# LEO_COTS_amps_rev1.net
KiCad netlist of a schematic drawn in Altium Designer
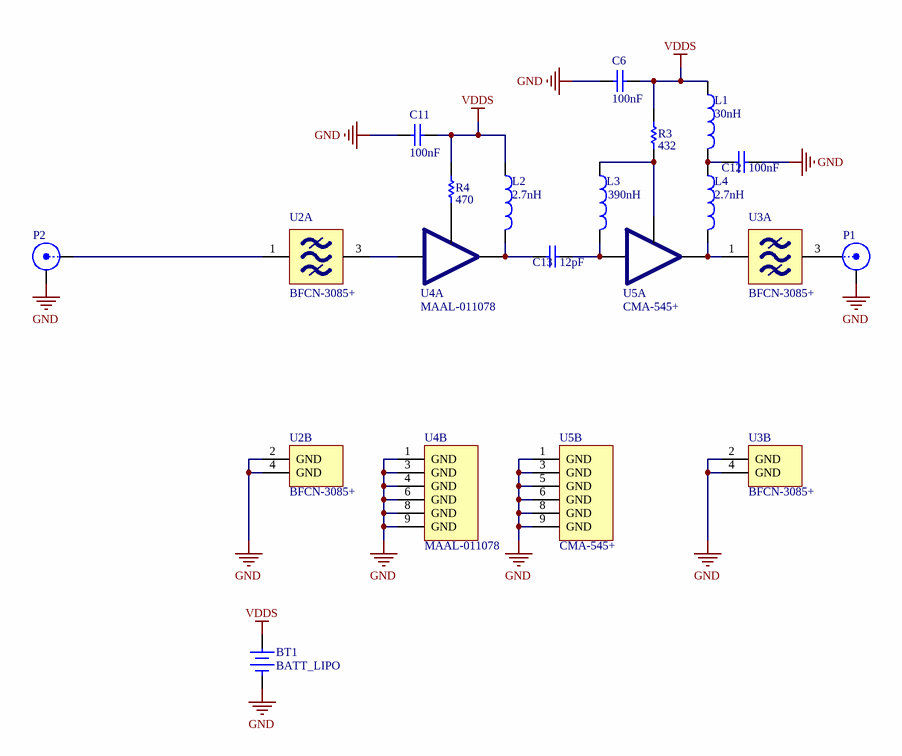
[diagram p0: LEO_COTS_amps_rev1.SchDoc]

(export (version "E")
  (design (tool "Eeschema 10.0.6"))
  (components
    (comp (ref "BT1")
      (value "BATT_LIPO")
      (footprint "LIPO_1cm_1cm")
      (libsource (lib "LEO_COTS_components") (part "BATT_LIPO"))
    )
    (comp (ref "C6")
      (value "100nF")
      (footprint "CAPC0603X04N")
      (description "CAP CER 100nF 0201")
      (fields (field (name "Comment") "CAP_0201"))
      (libsource (lib "LEO_COTS_components") (part "CAP_0201"))
    )
    (comp (ref "C11")
      (value "100nF")
      (footprint "CAPC0603X04N")
      (description "CAP CER 100nF 0201")
      (fields (field (name "Comment") "CAP_0201"))
      (libsource (lib "LEO_COTS_components") (part "CAP_0201"))
    )
    (comp (ref "C12")
      (value "100nF")
      (footprint "CAPC0603X04N")
      (description "CAP CER 100nF 0201")
      (fields (field (name "Comment") "CAP_0201"))
      (libsource (lib "LEO_COTS_components") (part "CAP_0201"))
    )
    (comp (ref "C13")
      (value "12pF")
      (footprint "CAPC0603X04N")
      (description "CAP CER 12pF 0201")
      (fields (field (name "Comment") "CAP_0201"))
      (libsource (lib "LEO_COTS_components") (part "CAP_0201"))
    )
    (comp (ref "L1")
      (value "30nH")
      (footprint "0402")
      (description "Inductor")
      (fields (field (name "PUBLISHER") "Altium Limited"))
      (libsource (lib "LEO_COTS_components") (part "Inductor"))
    )
    (comp (ref "L2")
      (value "2.7nH")
      (footprint "0402")
      (description "Inductor")
      (fields (field (name "PUBLISHER") "Altium Limited"))
      (libsource (lib "LEO_COTS_components") (part "Inductor"))
    )
    (comp (ref "L3")
      (value "390nH")
      (footprint "1608[0603]")
      (description "Inductor")
      (fields (field (name "PUBLISHER") "Altium Limited"))
      (libsource (lib "LEO_COTS_components") (part "Inductor"))
    )
    (comp (ref "L4")
      (value "2.7nH")
      (footprint "0402")
      (description "Inductor")
      (fields (field (name "PUBLISHER") "Altium Limited"))
      (libsource (lib "LEO_COTS_components") (part "Inductor"))
    )
    (comp (ref "P1")
      (value "1909763-1")
      (footprint "1909763-1")
      (description "CONN UMCC JACK STR 50OHM SMD")
      (libsource (lib "LEO_COTS_components") (part "1909763-1"))
    )
    (comp (ref "P2")
      (value "1909763-1")
      (footprint "1909763-1")
      (description "CONN UMCC JACK STR 50OHM SMD")
      (libsource (lib "LEO_COTS_components") (part "1909763-1"))
    )
    (comp (ref "R3")
      (value "432")
      (footprint "CAPC0603X04N")
      (description "RES 50 OHM 0201")
      (fields (field (name "Comment") "RES_0201") (field (name "PUBLISHER") "Altium Limited"))
      (libsource (lib "LEO_COTS_components") (part "Res Semi"))
    )
    (comp (ref "R4")
      (value "470")
      (footprint "CAPC0603X04N")
      (description "RES 50 OHM 0201")
      (fields (field (name "Comment") "RES_0201") (field (name "PUBLISHER") "Altium Limited"))
      (libsource (lib "LEO_COTS_components") (part "Res Semi"))
    )
    (comp (ref "U2")
      (value "BFCN-3085+")
      (footprint "FV1206")
      (description "2800 to 3400 MHz Band-Pass Filter")
      (libsource (lib "LEO_COTS_components") (part "BFCN-3085+"))
    )
    (comp (ref "U3")
      (value "BFCN-3085+")
      (footprint "FV1206")
      (description "2800 to 3400 MHz Band-Pass Filter")
      (libsource (lib "LEO_COTS_components") (part "BFCN-3085+"))
    )
    (comp (ref "U4")
      (value "MAAL-011078")
      (footprint "PDFN-8")
      (description "Wideband LNA")
      (libsource (lib "LEO_COTS_components") (part "MAAL-011078"))
    )
    (comp (ref "U5")
      (value "CMA-545+")
      (footprint "DL1721")
      (description "Wideband LNA")
      (libsource (lib "LEO_COTS_components") (part "CMA-545+"))
    )
  )
  (nets
    (net (code "1") (name "GND") (class "Default")
      (node (ref "BT1") (pin "2") (pinfunction "-_2") (pintype "passive"))
      (node (ref "C11") (pin "1") (pinfunction "1_1") (pintype "passive"))
      (node (ref "C12") (pin "1") (pinfunction "1_1") (pintype "passive"))
      (node (ref "C6") (pin "1") (pinfunction "1_1") (pintype "passive"))
      (node (ref "P1") (pin "2") (pinfunction "Y_2") (pintype "passive"))
      (node (ref "P2") (pin "2") (pinfunction "Y_2") (pintype "passive"))
      (node (ref "U2") (pin "2") (pinfunction "GND_2") (pintype "tri_state"))
      (node (ref "U2") (pin "4") (pinfunction "GND_4") (pintype "tri_state"))
      (node (ref "U3") (pin "2") (pinfunction "GND_2") (pintype "tri_state"))
      (node (ref "U3") (pin "4") (pinfunction "GND_4") (pintype "tri_state"))
      (node (ref "U4") (pin "1") (pinfunction "GND_1") (pintype "tri_state"))
      (node (ref "U4") (pin "3") (pinfunction "GND_3") (pintype "tri_state"))
      (node (ref "U4") (pin "4") (pinfunction "GND_4") (pintype "tri_state"))
      (node (ref "U4") (pin "6") (pinfunction "GND_6") (pintype "tri_state"))
      (node (ref "U4") (pin "8") (pinfunction "GND_8") (pintype "tri_state"))
      (node (ref "U4") (pin "9") (pinfunction "GND_9") (pintype "tri_state"))
      (node (ref "U5") (pin "1") (pinfunction "GND_1") (pintype "tri_state"))
      (node (ref "U5") (pin "3") (pinfunction "GND_3") (pintype "tri_state"))
      (node (ref "U5") (pin "5") (pinfunction "GND_5") (pintype "tri_state"))
      (node (ref "U5") (pin "6") (pinfunction "GND_6") (pintype "tri_state"))
      (node (ref "U5") (pin "8") (pinfunction "GND_8") (pintype "tri_state"))
      (node (ref "U5") (pin "9") (pinfunction "GND_9") (pintype "tri_state"))
    )
    (net (code "2") (name "Net-(C12-Pad2)") (class "Default")
      (node (ref "C12") (pin "2") (pinfunction "2_2") (pintype "passive"))
      (node (ref "L1") (pin "2") (pinfunction "2_2") (pintype "passive"))
      (node (ref "L4") (pin "1") (pinfunction "1_1") (pintype "passive"))
    )
    (net (code "3") (name "Net-(P1-X)") (class "Default")
      (node (ref "P1") (pin "1") (pinfunction "X_1") (pintype "passive"))
      (node (ref "U3") (pin "3") (pinfunction "OUT_3") (pintype "tri_state"))
    )
    (net (code "4") (name "Net-(P2-X)") (class "Default")
      (node (ref "P2") (pin "1") (pinfunction "X_1") (pintype "passive"))
      (node (ref "U2") (pin "1") (pinfunction "IN_1") (pintype "tri_state"))
    )
    (net (code "5") (name "Net-(U2A-OUT)") (class "Default")
      (node (ref "U2") (pin "3") (pinfunction "OUT_3") (pintype "tri_state"))
      (node (ref "U4") (pin "2") (pinfunction "IN_2") (pintype "tri_state"))
    )
    (net (code "6") (name "Net-(U3A-IN)") (class "Default")
      (node (ref "L4") (pin "2") (pinfunction "2_2") (pintype "passive"))
      (node (ref "U3") (pin "1") (pinfunction "IN_1") (pintype "tri_state"))
      (node (ref "U5") (pin "7") (pinfunction "OUT_7") (pintype "tri_state"))
    )
    (net (code "7") (name "Net-(U4A-BIAS)") (class "Default")
      (node (ref "R4") (pin "1") (pinfunction "1_1") (pintype "passive"))
      (node (ref "U4") (pin "5") (pinfunction "BIAS_5") (pintype "tri_state"))
    )
    (net (code "8") (name "Net-(U4A-OUT)") (class "Default")
      (node (ref "C13") (pin "2") (pinfunction "2_2") (pintype "passive"))
      (node (ref "L2") (pin "2") (pinfunction "2_2") (pintype "passive"))
      (node (ref "U4") (pin "7") (pinfunction "OUT_7") (pintype "tri_state"))
    )
    (net (code "9") (name "Net-(U5A-BIAS)") (class "Default")
      (node (ref "L3") (pin "1") (pinfunction "1_1") (pintype "passive"))
      (node (ref "R3") (pin "1") (pinfunction "1_1") (pintype "passive"))
      (node (ref "U5") (pin "4") (pinfunction "BIAS_4") (pintype "tri_state"))
    )
    (net (code "10") (name "Net-(U5A-IN)") (class "Default")
      (node (ref "C13") (pin "1") (pinfunction "1_1") (pintype "passive"))
      (node (ref "L3") (pin "2") (pinfunction "2_2") (pintype "passive"))
      (node (ref "U5") (pin "2") (pinfunction "IN_2") (pintype "tri_state"))
    )
    (net (code "11") (name "VDDS") (class "Default")
      (node (ref "BT1") (pin "1") (pinfunction "+_1") (pintype "passive"))
      (node (ref "C11") (pin "2") (pinfunction "2_2") (pintype "passive"))
      (node (ref "C6") (pin "2") (pinfunction "2_2") (pintype "passive"))
      (node (ref "L1") (pin "1") (pinfunction "1_1") (pintype "passive"))
      (node (ref "L2") (pin "1") (pinfunction "1_1") (pintype "passive"))
      (node (ref "R3") (pin "2") (pinfunction "2_2") (pintype "passive"))
      (node (ref "R4") (pin "2") (pinfunction "2_2") (pintype "passive"))
    )
  )
)
